# config-interface.net
KiCad netlist of a schematic drawn in Altium Designer
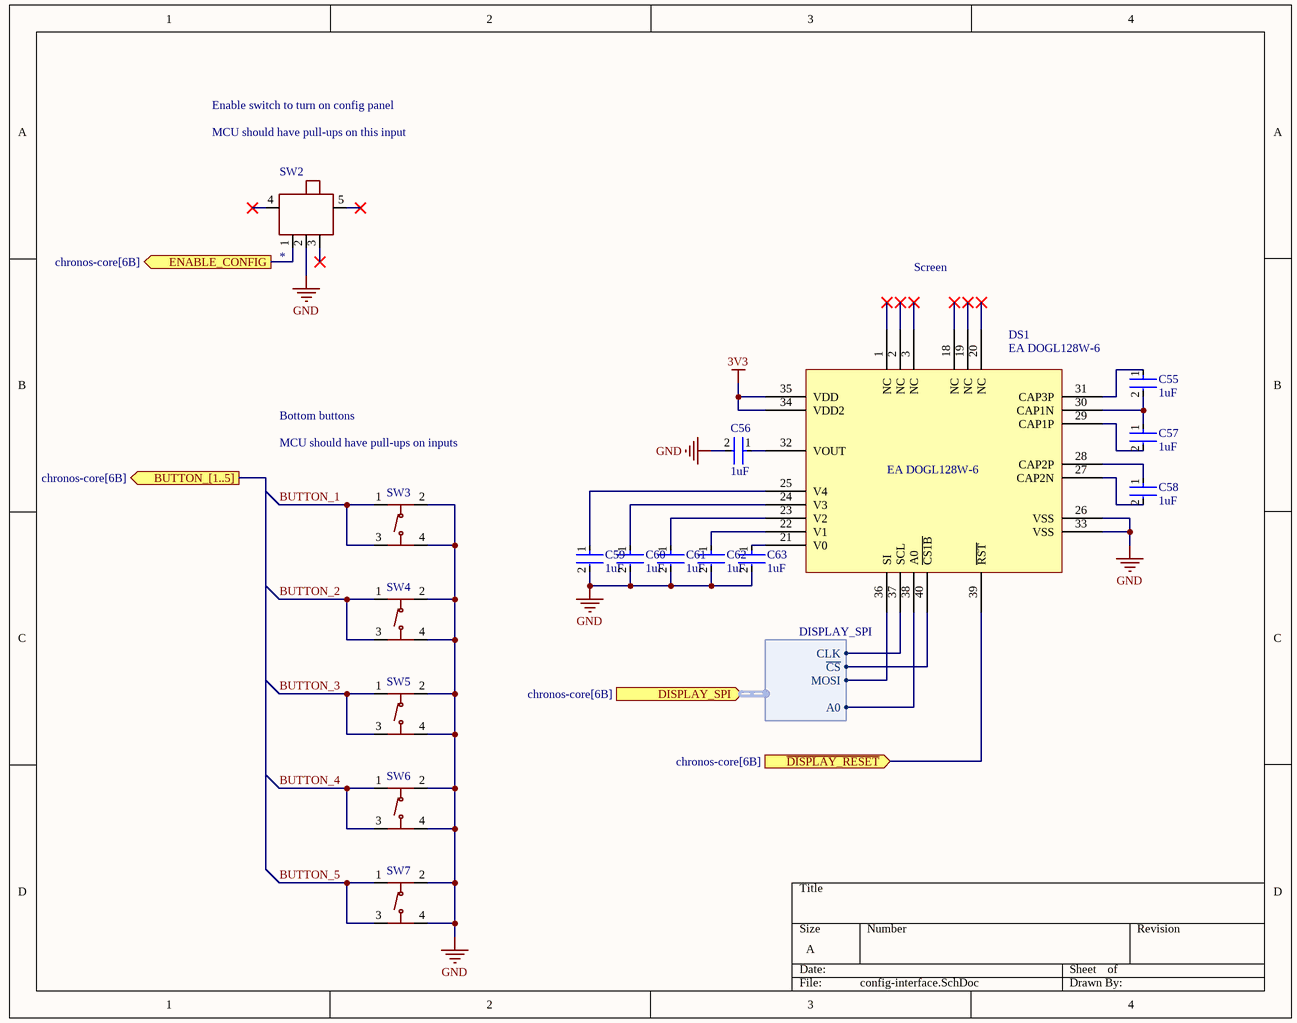
[diagram p0: config-interface.SchDoc]

(export (version "E")
  (design (tool "Eeschema 10.0.6"))
  (components
    (comp (ref "C55")
      (value "CL05A105KA5NQNC")
      (footprint "FP-CL542-IPC_C")
      (description "Cap Ceramic 1uF 25V X5R ±10% SMD 0402 +85°C Paper T/R")
      (fields (field (name "CAPACITANCE") "1uF") (field (name "TOLERANCE") "10%"))
      (libsource (lib "Altium Content Vault") (part "b4654b650e69147ec39a6b967a45e02"))
    )
    (comp (ref "C56")
      (value "CL05A105KA5NQNC")
      (footprint "FP-CL542-IPC_C")
      (description "Cap Ceramic 1uF 25V X5R ±10% SMD 0402 +85°C Paper T/R")
      (fields (field (name "CAPACITANCE") "1uF") (field (name "TOLERANCE") "10%"))
      (libsource (lib "Altium Content Vault") (part "b4654b650e69147ec39a6b967a45e02"))
    )
    (comp (ref "C57")
      (value "CL05A105KA5NQNC")
      (footprint "FP-CL542-IPC_C")
      (description "Cap Ceramic 1uF 25V X5R ±10% SMD 0402 +85°C Paper T/R")
      (fields (field (name "CAPACITANCE") "1uF") (field (name "TOLERANCE") "10%"))
      (libsource (lib "Altium Content Vault") (part "b4654b650e69147ec39a6b967a45e02"))
    )
    (comp (ref "C58")
      (value "CL05A105KA5NQNC")
      (footprint "FP-CL542-IPC_C")
      (description "Cap Ceramic 1uF 25V X5R ±10% SMD 0402 +85°C Paper T/R")
      (fields (field (name "CAPACITANCE") "1uF") (field (name "TOLERANCE") "10%"))
      (libsource (lib "Altium Content Vault") (part "b4654b650e69147ec39a6b967a45e02"))
    )
    (comp (ref "C59")
      (value "CL05A105KA5NQNC")
      (footprint "FP-CL542-IPC_C")
      (description "Cap Ceramic 1uF 25V X5R ±10% SMD 0402 +85°C Paper T/R")
      (fields (field (name "CAPACITANCE") "1uF") (field (name "TOLERANCE") "10%"))
      (libsource (lib "Altium Content Vault") (part "b4654b650e69147ec39a6b967a45e02"))
    )
    (comp (ref "C60")
      (value "CL05A105KA5NQNC")
      (footprint "FP-CL542-IPC_C")
      (description "Cap Ceramic 1uF 25V X5R ±10% SMD 0402 +85°C Paper T/R")
      (fields (field (name "CAPACITANCE") "1uF") (field (name "TOLERANCE") "10%"))
      (libsource (lib "Altium Content Vault") (part "b4654b650e69147ec39a6b967a45e02"))
    )
    (comp (ref "C61")
      (value "CL05A105KA5NQNC")
      (footprint "FP-CL542-IPC_C")
      (description "Cap Ceramic 1uF 25V X5R ±10% SMD 0402 +85°C Paper T/R")
      (fields (field (name "CAPACITANCE") "1uF") (field (name "TOLERANCE") "10%"))
      (libsource (lib "Altium Content Vault") (part "b4654b650e69147ec39a6b967a45e02"))
    )
    (comp (ref "C62")
      (value "CL05A105KA5NQNC")
      (footprint "FP-CL542-IPC_C")
      (description "Cap Ceramic 1uF 25V X5R ±10% SMD 0402 +85°C Paper T/R")
      (fields (field (name "CAPACITANCE") "1uF") (field (name "TOLERANCE") "10%"))
      (libsource (lib "Altium Content Vault") (part "b4654b650e69147ec39a6b967a45e02"))
    )
    (comp (ref "C63")
      (value "CL05A105KA5NQNC")
      (footprint "FP-CL542-IPC_C")
      (description "Cap Ceramic 1uF 25V X5R ±10% SMD 0402 +85°C Paper T/R")
      (fields (field (name "CAPACITANCE") "1uF") (field (name "TOLERANCE") "10%"))
      (libsource (lib "Altium Content Vault") (part "b4654b650e69147ec39a6b967a45e02"))
    )
    (comp (ref "DS1")
      (value "EA DOGL128W-6")
      (footprint "EA DOGL128W-6")
      (libsource (lib "EA DOGL128W-6") (part "EA DOGL128W-6"))
    )
    (comp (ref "SW2")
      (value "SS12D07VG4 087")
      (footprint "SS12D07VG4 087")
      (description "Slide Switches. SS12D07VG4 087")
      (fields
        (field (name "ALTIUM_VALUE") "*")
        (field (name "JLCPCB PART #") "C2939726")
        (field (name "MANUFACTURER") "SHOU HAN()")
      )
      (libsource (lib "SS12D07VG4 087") (part "SS12D07VG4 087"))
    )
    (comp (ref "SW3")
      (value "TS-1187A-B-A-B")
      (footprint "TS-1187A-B-A-B")
      (fields (field (name "JLCPCB PART #") "C318884") (field (name "MANUFACTURER") "XKB Connection"))
      (libsource (lib "TS-1187A-B-A-B") (part "TS-1187A-B-A-B"))
    )
    (comp (ref "SW4")
      (value "TS-1187A-B-A-B")
      (footprint "TS-1187A-B-A-B")
      (fields (field (name "JLCPCB PART #") "C318884") (field (name "MANUFACTURER") "XKB Connection"))
      (libsource (lib "TS-1187A-B-A-B") (part "TS-1187A-B-A-B"))
    )
    (comp (ref "SW5")
      (value "TS-1187A-B-A-B")
      (footprint "TS-1187A-B-A-B")
      (fields (field (name "JLCPCB PART #") "C318884") (field (name "MANUFACTURER") "XKB Connection"))
      (libsource (lib "TS-1187A-B-A-B") (part "TS-1187A-B-A-B"))
    )
    (comp (ref "SW6")
      (value "TS-1187A-B-A-B")
      (footprint "TS-1187A-B-A-B")
      (fields (field (name "JLCPCB PART #") "C318884") (field (name "MANUFACTURER") "XKB Connection"))
      (libsource (lib "TS-1187A-B-A-B") (part "TS-1187A-B-A-B"))
    )
    (comp (ref "SW7")
      (value "TS-1187A-B-A-B")
      (footprint "TS-1187A-B-A-B")
      (fields (field (name "JLCPCB PART #") "C318884") (field (name "MANUFACTURER") "XKB Connection"))
      (libsource (lib "TS-1187A-B-A-B") (part "TS-1187A-B-A-B"))
    )
  )
  (nets
    (net (code "2") (name "/A0") (class "Default")
      (node (ref "DS1") (pin "38") (pinfunction "A0_38") (pintype "passive"))
    )
    (net (code "3") (name "/BUTTON_1") (class "Default")
      (node (ref "SW3") (pin "1") (pinfunction "A_1") (pintype "passive"))
      (node (ref "SW3") (pin "3") (pinfunction "C_3") (pintype "passive"))
    )
    (net (code "4") (name "/BUTTON_2") (class "Default")
      (node (ref "SW4") (pin "1") (pinfunction "A_1") (pintype "passive"))
      (node (ref "SW4") (pin "3") (pinfunction "C_3") (pintype "passive"))
    )
    (net (code "5") (name "/BUTTON_3") (class "Default")
      (node (ref "SW5") (pin "1") (pinfunction "A_1") (pintype "passive"))
      (node (ref "SW5") (pin "3") (pinfunction "C_3") (pintype "passive"))
    )
    (net (code "6") (name "/BUTTON_4") (class "Default")
      (node (ref "SW6") (pin "1") (pinfunction "A_1") (pintype "passive"))
      (node (ref "SW6") (pin "3") (pinfunction "C_3") (pintype "passive"))
    )
    (net (code "7") (name "/BUTTON_5") (class "Default")
      (node (ref "SW7") (pin "1") (pinfunction "A_1") (pintype "passive"))
      (node (ref "SW7") (pin "3") (pinfunction "C_3") (pintype "passive"))
    )
    (net (code "9") (name "/CLK") (class "Default")
      (node (ref "DS1") (pin "37") (pinfunction "SCL_37") (pintype "passive"))
    )
    (net (code "10") (name "/DISPLAY_RESET") (class "Default")
      (node (ref "DS1") (pin "39") (pinfunction "RST_39") (pintype "passive"))
    )
    (net (code "11") (name "/ENABLE_CONFIG") (class "Default")
      (node (ref "SW2") (pin "1") (pinfunction "1_1") (pintype "passive"))
    )
    (net (code "12") (name "/MOSI") (class "Default")
      (node (ref "DS1") (pin "36") (pinfunction "SI_36") (pintype "passive"))
    )
    (net (code "14") (name "/~{CS}") (class "Default")
      (node (ref "DS1") (pin "40") (pinfunction "CS1B_40") (pintype "passive"))
    )
    (net (code "15") (name "3V3") (class "Default")
      (node (ref "DS1") (pin "34") (pinfunction "VDD2_34") (pintype "passive"))
      (node (ref "DS1") (pin "35") (pinfunction "VDD_35") (pintype "passive"))
    )
    (net (code "16") (name "GND") (class "Default")
      (node (ref "C56") (pin "2") (pinfunction "2_2") (pintype "passive"))
      (node (ref "C59") (pin "2") (pinfunction "2_2") (pintype "passive"))
      (node (ref "C60") (pin "2") (pinfunction "2_2") (pintype "passive"))
      (node (ref "C61") (pin "2") (pinfunction "2_2") (pintype "passive"))
      (node (ref "C62") (pin "2") (pinfunction "2_2") (pintype "passive"))
      (node (ref "C63") (pin "2") (pinfunction "2_2") (pintype "passive"))
      (node (ref "DS1") (pin "26") (pinfunction "VSS_26") (pintype "passive"))
      (node (ref "DS1") (pin "33") (pinfunction "VSS_33") (pintype "passive"))
      (node (ref "SW2") (pin "2") (pinfunction "2_2") (pintype "passive"))
      (node (ref "SW3") (pin "2") (pinfunction "B_2") (pintype "passive"))
      (node (ref "SW3") (pin "4") (pinfunction "D_4") (pintype "passive"))
      (node (ref "SW4") (pin "2") (pinfunction "B_2") (pintype "passive"))
      (node (ref "SW4") (pin "4") (pinfunction "D_4") (pintype "passive"))
      (node (ref "SW5") (pin "2") (pinfunction "B_2") (pintype "passive"))
      (node (ref "SW5") (pin "4") (pinfunction "D_4") (pintype "passive"))
      (node (ref "SW6") (pin "2") (pinfunction "B_2") (pintype "passive"))
      (node (ref "SW6") (pin "4") (pinfunction "D_4") (pintype "passive"))
      (node (ref "SW7") (pin "2") (pinfunction "B_2") (pintype "passive"))
      (node (ref "SW7") (pin "4") (pinfunction "D_4") (pintype "passive"))
    )
    (net (code "17") (name "Net-(DS1-CAP1N)") (class "Default")
      (node (ref "C55") (pin "2") (pinfunction "2_2") (pintype "passive"))
      (node (ref "C57") (pin "1") (pinfunction "1_1") (pintype "passive"))
      (node (ref "DS1") (pin "30") (pinfunction "CAP1N_30") (pintype "passive"))
    )
    (net (code "18") (name "Net-(DS1-CAP1P)") (class "Default")
      (node (ref "C57") (pin "2") (pinfunction "2_2") (pintype "passive"))
      (node (ref "DS1") (pin "29") (pinfunction "CAP1P_29") (pintype "passive"))
    )
    (net (code "19") (name "Net-(DS1-CAP2N)") (class "Default")
      (node (ref "C58") (pin "2") (pinfunction "2_2") (pintype "passive"))
      (node (ref "DS1") (pin "27") (pinfunction "CAP2N_27") (pintype "passive"))
    )
    (net (code "20") (name "Net-(DS1-CAP2P)") (class "Default")
      (node (ref "C58") (pin "1") (pinfunction "1_1") (pintype "passive"))
      (node (ref "DS1") (pin "28") (pinfunction "CAP2P_28") (pintype "passive"))
    )
    (net (code "21") (name "Net-(DS1-CAP3P)") (class "Default")
      (node (ref "C55") (pin "1") (pinfunction "1_1") (pintype "passive"))
      (node (ref "DS1") (pin "31") (pinfunction "CAP3P_31") (pintype "passive"))
    )
    (net (code "22") (name "Net-(DS1-V0)") (class "Default")
      (node (ref "C63") (pin "1") (pinfunction "1_1") (pintype "passive"))
      (node (ref "DS1") (pin "21") (pinfunction "V0_21") (pintype "passive"))
    )
    (net (code "23") (name "Net-(DS1-V1)") (class "Default")
      (node (ref "C62") (pin "1") (pinfunction "1_1") (pintype "passive"))
      (node (ref "DS1") (pin "22") (pinfunction "V1_22") (pintype "passive"))
    )
    (net (code "24") (name "Net-(DS1-V2)") (class "Default")
      (node (ref "C61") (pin "1") (pinfunction "1_1") (pintype "passive"))
      (node (ref "DS1") (pin "23") (pinfunction "V2_23") (pintype "passive"))
    )
    (net (code "25") (name "Net-(DS1-V3)") (class "Default")
      (node (ref "C60") (pin "1") (pinfunction "1_1") (pintype "passive"))
      (node (ref "DS1") (pin "24") (pinfunction "V3_24") (pintype "passive"))
    )
    (net (code "26") (name "Net-(DS1-V4)") (class "Default")
      (node (ref "C59") (pin "1") (pinfunction "1_1") (pintype "passive"))
      (node (ref "DS1") (pin "25") (pinfunction "V4_25") (pintype "passive"))
    )
    (net (code "27") (name "Net-(DS1-VOUT)") (class "Default")
      (node (ref "C56") (pin "1") (pinfunction "1_1") (pintype "passive"))
      (node (ref "DS1") (pin "32") (pinfunction "VOUT_32") (pintype "passive"))
    )
    (net (code "28") (name "unconnected-(DS1-NC-Pad1)") (class "Default")
      (node (ref "DS1") (pin "1") (pinfunction "NC_1") (pintype "passive+no_connect"))
    )
    (net (code "29") (name "unconnected-(DS1-NC-Pad2)") (class "Default")
      (node (ref "DS1") (pin "2") (pinfunction "NC_2") (pintype "passive+no_connect"))
    )
    (net (code "30") (name "unconnected-(DS1-NC-Pad3)") (class "Default")
      (node (ref "DS1") (pin "3") (pinfunction "NC_3") (pintype "passive+no_connect"))
    )
    (net (code "31") (name "unconnected-(DS1-NC-Pad18)") (class "Default")
      (node (ref "DS1") (pin "18") (pinfunction "NC_18") (pintype "passive+no_connect"))
    )
    (net (code "32") (name "unconnected-(DS1-NC-Pad19)") (class "Default")
      (node (ref "DS1") (pin "19") (pinfunction "NC_19") (pintype "passive+no_connect"))
    )
    (net (code "33") (name "unconnected-(DS1-NC-Pad20)") (class "Default")
      (node (ref "DS1") (pin "20") (pinfunction "NC_20") (pintype "passive+no_connect"))
    )
    (net (code "34") (name "unconnected-(SW2-Pad3)") (class "Default")
      (node (ref "SW2") (pin "3") (pinfunction "3_3") (pintype "passive+no_connect"))
    )
    (net (code "35") (name "unconnected-(SW2-Pad4)") (class "Default")
      (node (ref "SW2") (pin "4") (pinfunction "4_4") (pintype "passive+no_connect"))
    )
    (net (code "36") (name "unconnected-(SW2-Pad5)") (class "Default")
      (node (ref "SW2") (pin "5") (pinfunction "5_5") (pintype "passive+no_connect"))
    )
  )
)
